# MainBoard.net
KiCad netlist of a schematic drawn in Altium Designer
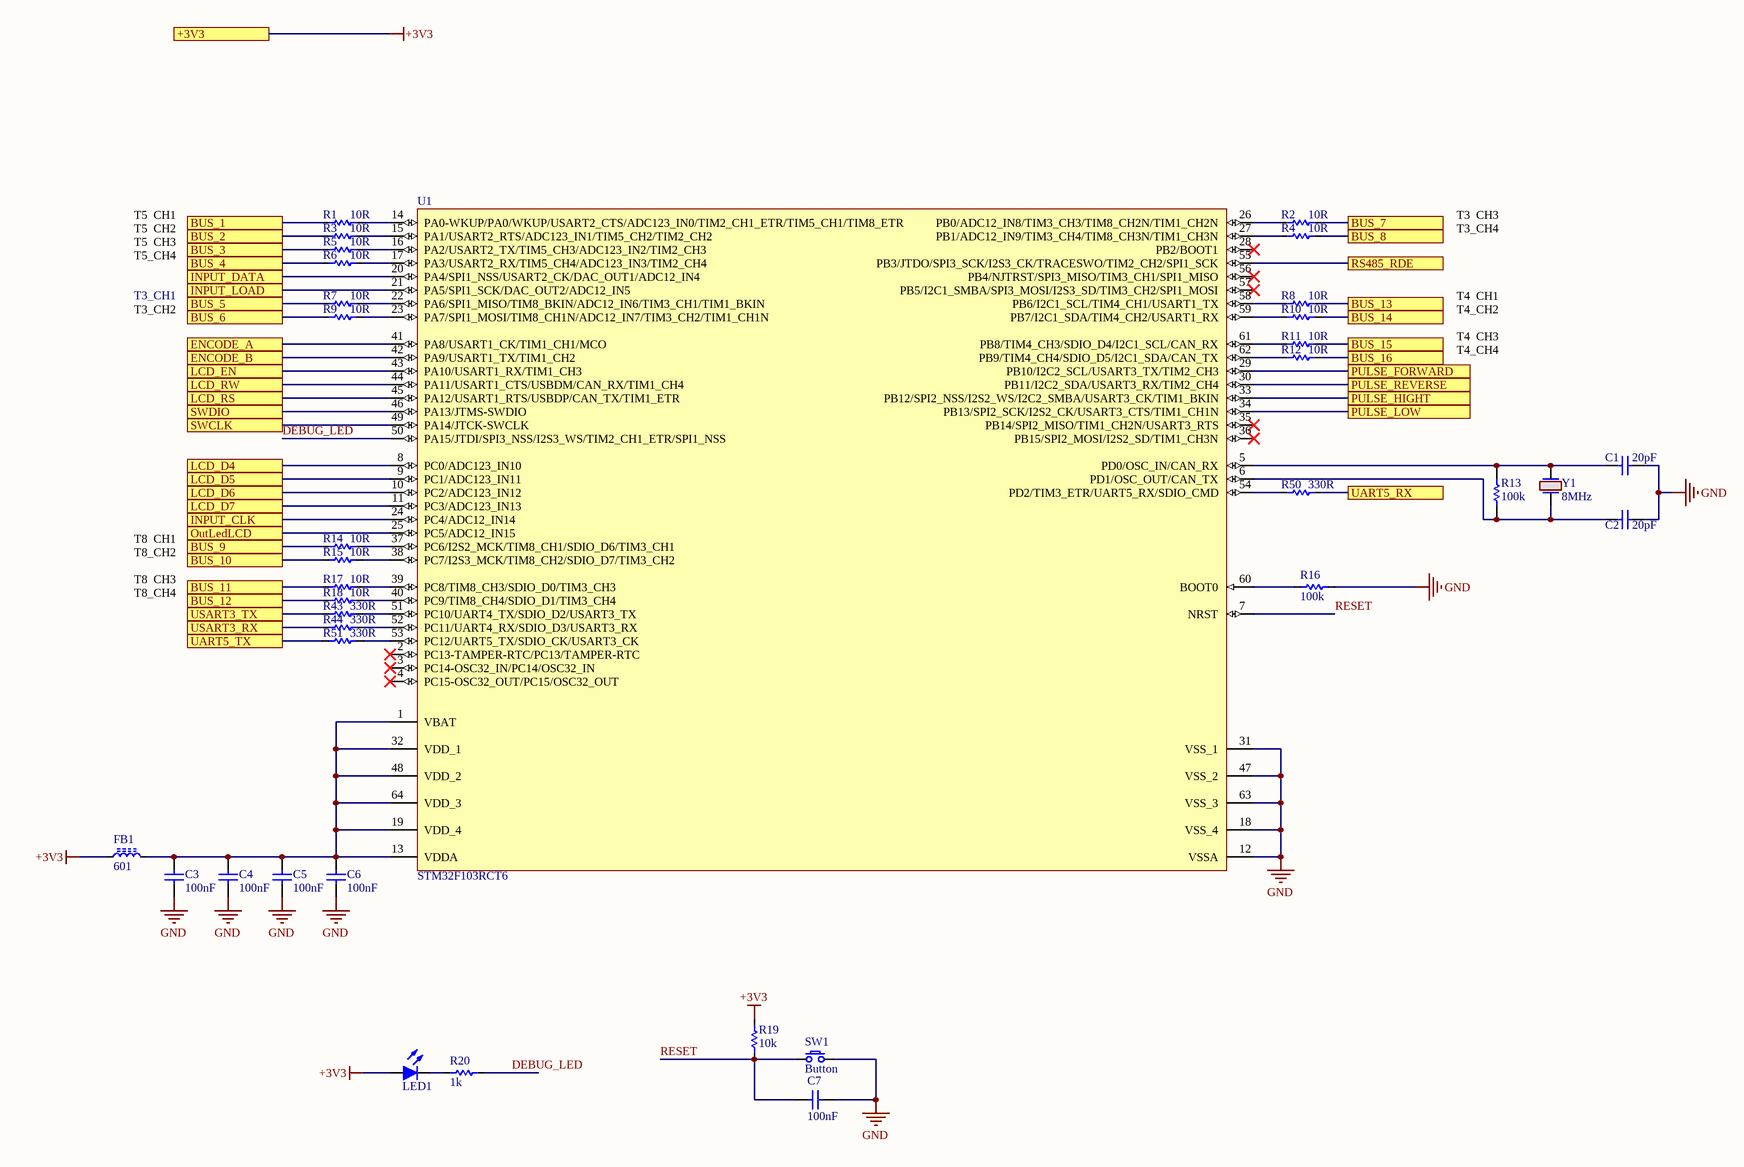
[diagram p0: MainBoard.SchDoc]

(export (version "E")
  (design (tool "Eeschema 10.0.6"))
  (components
    (comp (ref "C1")
      (value "20pF")
      (footprint "C 0603 (1608)")
      (description "Capacitor non-pol")
      (libsource (lib "BKIT4U_LIB") (part "Capacitor NP"))
    )
    (comp (ref "C2")
      (value "20pF")
      (footprint "C 0603 (1608)")
      (description "Capacitor non-pol")
      (libsource (lib "BKIT4U_LIB") (part "Capacitor NP"))
    )
    (comp (ref "C3")
      (value "100nF")
      (footprint "C 0805 (2012)")
      (description "Capacitor non-pol")
      (libsource (lib "BKIT4U_LIB_NEW") (part "Capacitor NP"))
    )
    (comp (ref "C4")
      (value "100nF")
      (footprint "C 0805 (2012)")
      (description "Capacitor non-pol")
      (libsource (lib "BKIT4U_LIB_NEW") (part "Capacitor NP"))
    )
    (comp (ref "C5")
      (value "100nF")
      (footprint "C 0805 (2012)")
      (description "Capacitor non-pol")
      (libsource (lib "BKIT4U_LIB_NEW") (part "Capacitor NP"))
    )
    (comp (ref "C6")
      (value "100nF")
      (footprint "C 0805 (2012)")
      (description "Capacitor non-pol")
      (libsource (lib "BKIT4U_LIB_NEW") (part "Capacitor NP"))
    )
    (comp (ref "C7")
      (value "100nF")
      (footprint "C 0805 (2012)")
      (description "Capacitor non-pol")
      (libsource (lib "BKIT4U_LIB_NEW") (part "Capacitor NP"))
    )
    (comp (ref "FB1")
      (value "601")
      (footprint "Inductor SMD 0805 (2012)")
      (description "Ferrite Breab")
      (libsource (lib "BKIT4U_LIB_NEW") (part "Ferrite Breab"))
    )
    (comp (ref "LED1")
      (value "Led")
      (footprint "Led SMD 0603")
      (description "Typical LED")
      (libsource (lib "BKIT4U_LIB_NEW") (part "Led"))
    )
    (comp (ref "R1")
      (value "10R")
      (footprint "R 0603 (1608)")
      (description "Resistor")
      (fields (field (name "PUBLISHER") "Altium Limited"))
      (libsource (lib "BKIT4U_LIB_NEW") (part "Resistor"))
    )
    (comp (ref "R2")
      (value "10R")
      (footprint "R 0603 (1608)")
      (description "Resistor")
      (fields (field (name "PUBLISHER") "Altium Limited"))
      (libsource (lib "BKIT4U_LIB_NEW") (part "Resistor"))
    )
    (comp (ref "R3")
      (value "10R")
      (footprint "R 0603 (1608)")
      (description "Resistor")
      (fields (field (name "PUBLISHER") "Altium Limited"))
      (libsource (lib "BKIT4U_LIB_NEW") (part "Resistor"))
    )
    (comp (ref "R4")
      (value "10R")
      (footprint "R 0603 (1608)")
      (description "Resistor")
      (fields (field (name "PUBLISHER") "Altium Limited"))
      (libsource (lib "BKIT4U_LIB_NEW") (part "Resistor"))
    )
    (comp (ref "R5")
      (value "10R")
      (footprint "R 0603 (1608)")
      (description "Resistor")
      (fields (field (name "PUBLISHER") "Altium Limited"))
      (libsource (lib "BKIT4U_LIB_NEW") (part "Resistor"))
    )
    (comp (ref "R6")
      (value "10R")
      (footprint "R 0603 (1608)")
      (description "Resistor")
      (fields (field (name "PUBLISHER") "Altium Limited"))
      (libsource (lib "BKIT4U_LIB_NEW") (part "Resistor"))
    )
    (comp (ref "R7")
      (value "10R")
      (footprint "R 0603 (1608)")
      (description "Resistor")
      (fields (field (name "PUBLISHER") "Altium Limited"))
      (libsource (lib "BKIT4U_LIB_NEW") (part "Resistor"))
    )
    (comp (ref "R8")
      (value "10R")
      (footprint "R 0603 (1608)")
      (description "Resistor")
      (fields (field (name "PUBLISHER") "Altium Limited"))
      (libsource (lib "BKIT4U_LIB_NEW") (part "Resistor"))
    )
    (comp (ref "R9")
      (value "10R")
      (footprint "R 0603 (1608)")
      (description "Resistor")
      (fields (field (name "PUBLISHER") "Altium Limited"))
      (libsource (lib "BKIT4U_LIB_NEW") (part "Resistor"))
    )
    (comp (ref "R10")
      (value "10R")
      (footprint "R 0603 (1608)")
      (description "Resistor")
      (fields (field (name "PUBLISHER") "Altium Limited"))
      (libsource (lib "BKIT4U_LIB_NEW") (part "Resistor"))
    )
    (comp (ref "R11")
      (value "10R")
      (footprint "R 0603 (1608)")
      (description "Resistor")
      (fields (field (name "PUBLISHER") "Altium Limited"))
      (libsource (lib "BKIT4U_LIB_NEW") (part "Resistor"))
    )
    (comp (ref "R12")
      (value "10R")
      (footprint "R 0603 (1608)")
      (description "Resistor")
      (fields (field (name "PUBLISHER") "Altium Limited"))
      (libsource (lib "BKIT4U_LIB_NEW") (part "Resistor"))
    )
    (comp (ref "R13")
      (value "100k")
      (footprint "R 0603 (1608)")
      (description "Resistor")
      (fields (field (name "PUBLISHER") "Altium Limited"))
      (libsource (lib "BKIT4U_LIB") (part "Resistor"))
    )
    (comp (ref "R14")
      (value "10R")
      (footprint "R 0603 (1608)")
      (description "Resistor")
      (fields (field (name "PUBLISHER") "Altium Limited"))
      (libsource (lib "BKIT4U_LIB_NEW") (part "Resistor"))
    )
    (comp (ref "R15")
      (value "10R")
      (footprint "R 0603 (1608)")
      (description "Resistor")
      (fields (field (name "PUBLISHER") "Altium Limited"))
      (libsource (lib "BKIT4U_LIB_NEW") (part "Resistor"))
    )
    (comp (ref "R16")
      (value "100k")
      (footprint "R 0603 (1608)")
      (description "Resistor")
      (fields (field (name "PUBLISHER") "Altium Limited"))
      (libsource (lib "BKIT4U_LIB_NEW") (part "Resistor"))
    )
    (comp (ref "R17")
      (value "10R")
      (footprint "R 0603 (1608)")
      (description "Resistor")
      (fields (field (name "PUBLISHER") "Altium Limited"))
      (libsource (lib "BKIT4U_LIB_NEW") (part "Resistor"))
    )
    (comp (ref "R18")
      (value "10R")
      (footprint "R 0603 (1608)")
      (description "Resistor")
      (fields (field (name "PUBLISHER") "Altium Limited"))
      (libsource (lib "BKIT4U_LIB_NEW") (part "Resistor"))
    )
    (comp (ref "R19")
      (value "10k")
      (footprint "R 0805 (2012)")
      (description "Resistor")
      (fields (field (name "PUBLISHER") "Altium Limited"))
      (libsource (lib "BKIT4U_LIB_NEW") (part "Resistor"))
    )
    (comp (ref "R20")
      (value "1k")
      (footprint "R 0603 (1608)")
      (description "Resistor")
      (fields (field (name "PUBLISHER") "Altium Limited"))
      (libsource (lib "BKIT4U_LIB_NEW") (part "Resistor"))
    )
    (comp (ref "R43")
      (value "330R")
      (footprint "R 0603 (1608)")
      (description "Resistor")
      (fields (field (name "PUBLISHER") "Altium Limited"))
      (libsource (lib "BKIT4U_LIB_NEW") (part "Resistor"))
    )
    (comp (ref "R44")
      (value "330R")
      (footprint "R 0603 (1608)")
      (description "Resistor")
      (fields (field (name "PUBLISHER") "Altium Limited"))
      (libsource (lib "BKIT4U_LIB_NEW") (part "Resistor"))
    )
    (comp (ref "R50")
      (value "330R")
      (footprint "R 0603 (1608)")
      (description "Resistor")
      (fields (field (name "PUBLISHER") "Altium Limited"))
      (libsource (lib "BKIT4U_LIB_NEW") (part "Resistor"))
    )
    (comp (ref "R51")
      (value "330R")
      (footprint "R 0603 (1608)")
      (description "Resistor")
      (fields (field (name "PUBLISHER") "Altium Limited"))
      (libsource (lib "BKIT4U_LIB_NEW") (part "Resistor"))
    )
    (comp (ref "SW1")
      (value "Button")
      (footprint "SW/2/SMD")
      (description "Tact switch 2 pin")
      (libsource (lib "BKIT4U_LIB_NEW") (part "SW SPST"))
    )
    (comp (ref "U1")
      (value "STM32F103RCT6")
      (footprint "LQFP64_N")
      (libsource (lib "BKIT4U_LIB_NEW") (part "STM32F103RCT6"))
    )
    (comp (ref "Y1")
      (value "8MHz")
      (footprint "Crystal SMD FC135")
      (libsource (lib "BKIT4U_LIB") (part "Crystal"))
    )
  )
  (nets
    (net (code "1") (name "+3V3") (class "Default")
      (node (ref "FB1") (pin "1") (pinfunction "1_1") (pintype "passive"))
      (node (ref "LED1") (pin "2") (pinfunction "A_2") (pintype "passive"))
      (node (ref "R19") (pin "2") (pinfunction "2_2") (pintype "passive"))
    )
    (net (code "2") (name "/BUS_1") (class "Default")
      (node (ref "R1") (pin "1") (pinfunction "1_1") (pintype "passive"))
    )
    (net (code "3") (name "/BUS_2") (class "Default")
      (node (ref "R3") (pin "1") (pinfunction "1_1") (pintype "passive"))
    )
    (net (code "4") (name "/BUS_3") (class "Default")
      (node (ref "R5") (pin "1") (pinfunction "1_1") (pintype "passive"))
    )
    (net (code "5") (name "/BUS_4") (class "Default")
      (node (ref "R6") (pin "1") (pinfunction "1_1") (pintype "passive"))
    )
    (net (code "6") (name "/BUS_5") (class "Default")
      (node (ref "R7") (pin "1") (pinfunction "1_1") (pintype "passive"))
    )
    (net (code "7") (name "/BUS_6") (class "Default")
      (node (ref "R9") (pin "1") (pinfunction "1_1") (pintype "passive"))
    )
    (net (code "8") (name "/BUS_7") (class "Default")
      (node (ref "R2") (pin "2") (pinfunction "2_2") (pintype "passive"))
    )
    (net (code "9") (name "/BUS_8") (class "Default")
      (node (ref "R4") (pin "2") (pinfunction "2_2") (pintype "passive"))
    )
    (net (code "10") (name "/BUS_9") (class "Default")
      (node (ref "R14") (pin "1") (pinfunction "1_1") (pintype "passive"))
    )
    (net (code "11") (name "/BUS_10") (class "Default")
      (node (ref "R15") (pin "1") (pinfunction "1_1") (pintype "passive"))
    )
    (net (code "12") (name "/BUS_11") (class "Default")
      (node (ref "R17") (pin "1") (pinfunction "1_1") (pintype "passive"))
    )
    (net (code "13") (name "/BUS_12") (class "Default")
      (node (ref "R18") (pin "1") (pinfunction "1_1") (pintype "passive"))
    )
    (net (code "14") (name "/BUS_13") (class "Default")
      (node (ref "R8") (pin "2") (pinfunction "2_2") (pintype "passive"))
    )
    (net (code "15") (name "/BUS_14") (class "Default")
      (node (ref "R10") (pin "2") (pinfunction "2_2") (pintype "passive"))
    )
    (net (code "16") (name "/BUS_15") (class "Default")
      (node (ref "R11") (pin "2") (pinfunction "2_2") (pintype "passive"))
    )
    (net (code "17") (name "/BUS_16") (class "Default")
      (node (ref "R12") (pin "2") (pinfunction "2_2") (pintype "passive"))
    )
    (net (code "18") (name "/DEBUG_LED") (class "Default")
      (node (ref "R20") (pin "2") (pinfunction "2_2") (pintype "passive"))
      (node (ref "U1") (pin "50") (pinfunction "PA15/JTDI/SPI3_NSS/I2S3_WS/TIM2_CH1_ETR/SPI1_NSS_50") (pintype "bidirectional"))
    )
    (net (code "19") (name "/ENCODE_A") (class "Default")
      (node (ref "U1") (pin "41") (pinfunction "PA8/USART1_CK/TIM1_CH1/MCO_41") (pintype "bidirectional"))
    )
    (net (code "20") (name "/ENCODE_B") (class "Default")
      (node (ref "U1") (pin "42") (pinfunction "PA9/USART1_TX/TIM1_CH2_42") (pintype "bidirectional"))
    )
    (net (code "21") (name "/INPUT_CLK") (class "Default")
      (node (ref "U1") (pin "24") (pinfunction "PC4/ADC12_IN14_24") (pintype "bidirectional"))
    )
    (net (code "22") (name "/INPUT_DATA") (class "Default")
      (node (ref "U1") (pin "20") (pinfunction "PA4/SPI1_NSS/USART2_CK/DAC_OUT1/ADC12_IN4_20") (pintype "bidirectional"))
    )
    (net (code "23") (name "/INPUT_LOAD") (class "Default")
      (node (ref "U1") (pin "21") (pinfunction "PA5/SPI1_SCK/DAC_OUT2/ADC12_IN5_21") (pintype "bidirectional"))
    )
    (net (code "24") (name "/LCD_D4") (class "Default")
      (node (ref "U1") (pin "8") (pinfunction "PC0/ADC123_IN10_8") (pintype "bidirectional"))
    )
    (net (code "25") (name "/LCD_D5") (class "Default")
      (node (ref "U1") (pin "9") (pinfunction "PC1/ADC123_IN11_9") (pintype "bidirectional"))
    )
    (net (code "26") (name "/LCD_D6") (class "Default")
      (node (ref "U1") (pin "10") (pinfunction "PC2/ADC123_IN12_10") (pintype "bidirectional"))
    )
    (net (code "27") (name "/LCD_D7") (class "Default")
      (node (ref "U1") (pin "11") (pinfunction "PC3/ADC123_IN13_11") (pintype "bidirectional"))
    )
    (net (code "28") (name "/LCD_EN") (class "Default")
      (node (ref "U1") (pin "43") (pinfunction "PA10/USART1_RX/TIM1_CH3_43") (pintype "bidirectional"))
    )
    (net (code "29") (name "/LCD_RS") (class "Default")
      (node (ref "U1") (pin "45") (pinfunction "PA12/USART1_RTS/USBDP/CAN_TX/TIM1_ETR_45") (pintype "bidirectional"))
    )
    (net (code "30") (name "/LCD_RW") (class "Default")
      (node (ref "U1") (pin "44") (pinfunction "PA11/USART1_CTS/USBDM/CAN_RX/TIM1_CH4_44") (pintype "bidirectional"))
    )
    (net (code "31") (name "/OutLedLCD") (class "Default")
      (node (ref "U1") (pin "25") (pinfunction "PC5/ADC12_IN15_25") (pintype "bidirectional"))
    )
    (net (code "32") (name "/PULSE_FORWARD") (class "Default")
      (node (ref "U1") (pin "29") (pinfunction "PB10/I2C2_SCL/USART3_TX/TIM2_CH3_29") (pintype "bidirectional"))
    )
    (net (code "33") (name "/PULSE_HIGHT") (class "Default")
      (node (ref "U1") (pin "33") (pinfunction "PB12/SPI2_NSS/I2S2_WS/I2C2_SMBA/USART3_CK/TIM1_BKIN_33") (pintype "bidirectional"))
    )
    (net (code "34") (name "/PULSE_LOW") (class "Default")
      (node (ref "U1") (pin "34") (pinfunction "PB13/SPI2_SCK/I2S2_CK/USART3_CTS/TIM1_CH1N_34") (pintype "bidirectional"))
    )
    (net (code "35") (name "/PULSE_REVERSE") (class "Default")
      (node (ref "U1") (pin "30") (pinfunction "PB11/I2C2_SDA/USART3_RX/TIM2_CH4_30") (pintype "bidirectional"))
    )
    (net (code "36") (name "/RESET") (class "Default")
      (node (ref "C7") (pin "1") (pinfunction "1_1") (pintype "passive"))
      (node (ref "R19") (pin "1") (pinfunction "1_1") (pintype "passive"))
      (node (ref "SW1") (pin "1") (pinfunction "1_1") (pintype "passive"))
      (node (ref "U1") (pin "7") (pinfunction "NRST_7") (pintype "bidirectional"))
    )
    (net (code "37") (name "/RS485_RDE") (class "Default")
      (node (ref "U1") (pin "55") (pinfunction "PB3/JTDO/SPI3_SCK/I2S3_CK/TRACESWO/TIM2_CH2/SPI1_SCK_55") (pintype "bidirectional"))
    )
    (net (code "38") (name "/SWCLK") (class "Default")
      (node (ref "U1") (pin "49") (pinfunction "PA14/JTCK-SWCLK_49") (pintype "bidirectional"))
    )
    (net (code "39") (name "/SWDIO") (class "Default")
      (node (ref "U1") (pin "46") (pinfunction "PA13/JTMS-SWDIO_46") (pintype "bidirectional"))
    )
    (net (code "40") (name "/UART5_RX") (class "Default")
      (node (ref "R50") (pin "2") (pinfunction "2_2") (pintype "passive"))
    )
    (net (code "41") (name "/UART5_TX") (class "Default")
      (node (ref "R51") (pin "1") (pinfunction "1_1") (pintype "passive"))
    )
    (net (code "42") (name "/USART3_RX") (class "Default")
      (node (ref "R44") (pin "1") (pinfunction "1_1") (pintype "passive"))
    )
    (net (code "43") (name "/USART3_TX") (class "Default")
      (node (ref "R43") (pin "1") (pinfunction "1_1") (pintype "passive"))
    )
    (net (code "44") (name "GND") (class "Default")
      (node (ref "C1") (pin "2") (pinfunction "2_2") (pintype "passive"))
      (node (ref "C2") (pin "2") (pinfunction "2_2") (pintype "passive"))
      (node (ref "C3") (pin "2") (pinfunction "2_2") (pintype "passive"))
      (node (ref "C4") (pin "2") (pinfunction "2_2") (pintype "passive"))
      (node (ref "C5") (pin "2") (pinfunction "2_2") (pintype "passive"))
      (node (ref "C6") (pin "2") (pinfunction "2_2") (pintype "passive"))
      (node (ref "C7") (pin "2") (pinfunction "2_2") (pintype "passive"))
      (node (ref "R16") (pin "2") (pinfunction "2_2") (pintype "passive"))
      (node (ref "SW1") (pin "2") (pinfunction "2_2") (pintype "passive"))
      (node (ref "U1") (pin "12") (pinfunction "VSSA_12") (pintype "power_in"))
      (node (ref "U1") (pin "18") (pinfunction "VSS_4_18") (pintype "power_in"))
      (node (ref "U1") (pin "31") (pinfunction "VSS_1_31") (pintype "power_in"))
      (node (ref "U1") (pin "47") (pinfunction "VSS_2_47") (pintype "power_in"))
      (node (ref "U1") (pin "63") (pinfunction "VSS_3_63") (pintype "power_in"))
    )
    (net (code "45") (name "Net-(LED1-K)") (class "Default")
      (node (ref "LED1") (pin "1") (pinfunction "K_1") (pintype "passive"))
      (node (ref "R20") (pin "1") (pinfunction "1_1") (pintype "passive"))
    )
    (net (code "46") (name "Net-(U1-BOOT0)") (class "Default")
      (node (ref "R16") (pin "1") (pinfunction "1_1") (pintype "passive"))
      (node (ref "U1") (pin "60") (pinfunction "BOOT0_60") (pintype "input"))
    )
    (net (code "47") (name "Net-(U1-PA0-WKUP{slash}PA0{slash}WKUP{slash}USART2_CTS{slash}ADC123_IN0{slash}TIM2_CH1_ETR{slash}TIM5_CH1{slash}TIM8_ETR)") (class "Default")
      (node (ref "R1") (pin "2") (pinfunction "2_2") (pintype "passive"))
      (node (ref "U1") (pin "14") (pinfunction "PA0-WKUP/PA0/WKUP/USART2_CTS/ADC123_IN0/TIM2_CH1_ETR/TIM5_CH1/TIM8_ETR_14") (pintype "bidirectional"))
    )
    (net (code "48") (name "Net-(U1-PA1{slash}USART2_RTS{slash}ADC123_IN1{slash}TIM5_CH2{slash}TIM2_CH2)") (class "Default")
      (node (ref "R3") (pin "2") (pinfunction "2_2") (pintype "passive"))
      (node (ref "U1") (pin "15") (pinfunction "PA1/USART2_RTS/ADC123_IN1/TIM5_CH2/TIM2_CH2_15") (pintype "bidirectional"))
    )
    (net (code "49") (name "Net-(U1-PA2{slash}USART2_TX{slash}TIM5_CH3{slash}ADC123_IN2{slash}TIM2_CH3)") (class "Default")
      (node (ref "R5") (pin "2") (pinfunction "2_2") (pintype "passive"))
      (node (ref "U1") (pin "16") (pinfunction "PA2/USART2_TX/TIM5_CH3/ADC123_IN2/TIM2_CH3_16") (pintype "bidirectional"))
    )
    (net (code "50") (name "Net-(U1-PA3{slash}USART2_RX{slash}TIM5_CH4{slash}ADC123_IN3{slash}TIM2_CH4)") (class "Default")
      (node (ref "R6") (pin "2") (pinfunction "2_2") (pintype "passive"))
      (node (ref "U1") (pin "17") (pinfunction "PA3/USART2_RX/TIM5_CH4/ADC123_IN3/TIM2_CH4_17") (pintype "bidirectional"))
    )
    (net (code "51") (name "Net-(U1-PA6{slash}SPI1_MISO{slash}TIM8_BKIN{slash}ADC12_IN6{slash}TIM3_CH1{slash}TIM1_BKIN)") (class "Default")
      (node (ref "R7") (pin "2") (pinfunction "2_2") (pintype "passive"))
      (node (ref "U1") (pin "22") (pinfunction "PA6/SPI1_MISO/TIM8_BKIN/ADC12_IN6/TIM3_CH1/TIM1_BKIN_22") (pintype "bidirectional"))
    )
    (net (code "52") (name "Net-(U1-PA7{slash}SPI1_MOSI{slash}TIM8_CH1N{slash}ADC12_IN7{slash}TIM3_CH2{slash}TIM1_CH1N)") (class "Default")
      (node (ref "R9") (pin "2") (pinfunction "2_2") (pintype "passive"))
      (node (ref "U1") (pin "23") (pinfunction "PA7/SPI1_MOSI/TIM8_CH1N/ADC12_IN7/TIM3_CH2/TIM1_CH1N_23") (pintype "bidirectional"))
    )
    (net (code "53") (name "Net-(U1-PB0{slash}ADC12_IN8{slash}TIM3_CH3{slash}TIM8_CH2N{slash}TIM1_CH2N)") (class "Default")
      (node (ref "R2") (pin "1") (pinfunction "1_1") (pintype "passive"))
      (node (ref "U1") (pin "26") (pinfunction "PB0/ADC12_IN8/TIM3_CH3/TIM8_CH2N/TIM1_CH2N_26") (pintype "bidirectional"))
    )
    (net (code "54") (name "Net-(U1-PB1{slash}ADC12_IN9{slash}TIM3_CH4{slash}TIM8_CH3N{slash}TIM1_CH3N)") (class "Default")
      (node (ref "R4") (pin "1") (pinfunction "1_1") (pintype "passive"))
      (node (ref "U1") (pin "27") (pinfunction "PB1/ADC12_IN9/TIM3_CH4/TIM8_CH3N/TIM1_CH3N_27") (pintype "bidirectional"))
    )
    (net (code "55") (name "Net-(U1-PB6{slash}I2C1_SCL{slash}TIM4_CH1{slash}USART1_TX)") (class "Default")
      (node (ref "R8") (pin "1") (pinfunction "1_1") (pintype "passive"))
      (node (ref "U1") (pin "58") (pinfunction "PB6/I2C1_SCL/TIM4_CH1/USART1_TX_58") (pintype "bidirectional"))
    )
    (net (code "56") (name "Net-(U1-PB7{slash}I2C1_SDA{slash}TIM4_CH2{slash}USART1_RX)") (class "Default")
      (node (ref "R10") (pin "1") (pinfunction "1_1") (pintype "passive"))
      (node (ref "U1") (pin "59") (pinfunction "PB7/I2C1_SDA/TIM4_CH2/USART1_RX_59") (pintype "bidirectional"))
    )
    (net (code "57") (name "Net-(U1-PB8{slash}TIM4_CH3{slash}SDIO_D4{slash}I2C1_SCL{slash}CAN_RX)") (class "Default")
      (node (ref "R11") (pin "1") (pinfunction "1_1") (pintype "passive"))
      (node (ref "U1") (pin "61") (pinfunction "PB8/TIM4_CH3/SDIO_D4/I2C1_SCL/CAN_RX_61") (pintype "bidirectional"))
    )
    (net (code "58") (name "Net-(U1-PB9{slash}TIM4_CH4{slash}SDIO_D5{slash}I2C1_SDA{slash}CAN_TX)") (class "Default")
      (node (ref "R12") (pin "1") (pinfunction "1_1") (pintype "passive"))
      (node (ref "U1") (pin "62") (pinfunction "PB9/TIM4_CH4/SDIO_D5/I2C1_SDA/CAN_TX_62") (pintype "bidirectional"))
    )
    (net (code "59") (name "Net-(U1-PC6{slash}I2S2_MCK{slash}TIM8_CH1{slash}SDIO_D6{slash}TIM3_CH1)") (class "Default")
      (node (ref "R14") (pin "2") (pinfunction "2_2") (pintype "passive"))
      (node (ref "U1") (pin "37") (pinfunction "PC6/I2S2_MCK/TIM8_CH1/SDIO_D6/TIM3_CH1_37") (pintype "bidirectional"))
    )
    (net (code "60") (name "Net-(U1-PC7{slash}I2S3_MCK{slash}TIM8_CH2{slash}SDIO_D7{slash}TIM3_CH2)") (class "Default")
      (node (ref "R15") (pin "2") (pinfunction "2_2") (pintype "passive"))
      (node (ref "U1") (pin "38") (pinfunction "PC7/I2S3_MCK/TIM8_CH2/SDIO_D7/TIM3_CH2_38") (pintype "bidirectional"))
    )
    (net (code "61") (name "Net-(U1-PC8{slash}TIM8_CH3{slash}SDIO_D0{slash}TIM3_CH3)") (class "Default")
      (node (ref "R17") (pin "2") (pinfunction "2_2") (pintype "passive"))
      (node (ref "U1") (pin "39") (pinfunction "PC8/TIM8_CH3/SDIO_D0/TIM3_CH3_39") (pintype "bidirectional"))
    )
    (net (code "62") (name "Net-(U1-PC9{slash}TIM8_CH4{slash}SDIO_D1{slash}TIM3_CH4)") (class "Default")
      (node (ref "R18") (pin "2") (pinfunction "2_2") (pintype "passive"))
      (node (ref "U1") (pin "40") (pinfunction "PC9/TIM8_CH4/SDIO_D1/TIM3_CH4_40") (pintype "bidirectional"))
    )
    (net (code "63") (name "Net-(U1-PC10{slash}UART4_TX{slash}SDIO_D2{slash}USART3_TX)") (class "Default")
      (node (ref "R43") (pin "2") (pinfunction "2_2") (pintype "passive"))
      (node (ref "U1") (pin "51") (pinfunction "PC10/UART4_TX/SDIO_D2/USART3_TX_51") (pintype "bidirectional"))
    )
    (net (code "64") (name "Net-(U1-PC11{slash}UART4_RX{slash}SDIO_D3{slash}USART3_RX)") (class "Default")
      (node (ref "R44") (pin "2") (pinfunction "2_2") (pintype "passive"))
      (node (ref "U1") (pin "52") (pinfunction "PC11/UART4_RX/SDIO_D3/USART3_RX_52") (pintype "bidirectional"))
    )
    (net (code "65") (name "Net-(U1-PC12{slash}UART5_TX{slash}SDIO_CK{slash}USART3_CK)") (class "Default")
      (node (ref "R51") (pin "2") (pinfunction "2_2") (pintype "passive"))
      (node (ref "U1") (pin "53") (pinfunction "PC12/UART5_TX/SDIO_CK/USART3_CK_53") (pintype "bidirectional"))
    )
    (net (code "66") (name "Net-(U1-PD0{slash}OSC_IN{slash}CAN_RX)") (class "Default")
      (node (ref "C1") (pin "1") (pinfunction "1_1") (pintype "passive"))
      (node (ref "R13") (pin "2") (pinfunction "2_2") (pintype "passive"))
      (node (ref "U1") (pin "5") (pinfunction "PD0/OSC_IN/CAN_RX_5") (pintype "bidirectional"))
      (node (ref "Y1") (pin "2") (pinfunction "2_2") (pintype "passive"))
    )
    (net (code "67") (name "Net-(U1-PD1{slash}OSC_OUT{slash}CAN_TX)") (class "Default")
      (node (ref "C2") (pin "1") (pinfunction "1_1") (pintype "passive"))
      (node (ref "R13") (pin "1") (pinfunction "1_1") (pintype "passive"))
      (node (ref "U1") (pin "6") (pinfunction "PD1/OSC_OUT/CAN_TX_6") (pintype "bidirectional"))
      (node (ref "Y1") (pin "1") (pinfunction "1_1") (pintype "passive"))
    )
    (net (code "68") (name "Net-(U1-PD2{slash}TIM3_ETR{slash}UART5_RX{slash}SDIO_CMD)") (class "Default")
      (node (ref "R50") (pin "1") (pinfunction "1_1") (pintype "passive"))
      (node (ref "U1") (pin "54") (pinfunction "PD2/TIM3_ETR/UART5_RX/SDIO_CMD_54") (pintype "bidirectional"))
    )
    (net (code "69") (name "Net-(U1-VBAT)") (class "Default")
      (node (ref "C3") (pin "1") (pinfunction "1_1") (pintype "passive"))
      (node (ref "C4") (pin "1") (pinfunction "1_1") (pintype "passive"))
      (node (ref "C5") (pin "1") (pinfunction "1_1") (pintype "passive"))
      (node (ref "C6") (pin "1") (pinfunction "1_1") (pintype "passive"))
      (node (ref "FB1") (pin "2") (pinfunction "2_2") (pintype "passive"))
      (node (ref "U1") (pin "1") (pinfunction "VBAT_1") (pintype "power_in"))
      (node (ref "U1") (pin "13") (pinfunction "VDDA_13") (pintype "power_in"))
      (node (ref "U1") (pin "19") (pinfunction "VDD_4_19") (pintype "power_in"))
      (node (ref "U1") (pin "32") (pinfunction "VDD_1_32") (pintype "power_in"))
      (node (ref "U1") (pin "48") (pinfunction "VDD_2_48") (pintype "power_in"))
      (node (ref "U1") (pin "64") (pinfunction "VDD_3_64") (pintype "power_in"))
    )
    (net (code "70") (name "unconnected-(U1-PB2{slash}BOOT1-Pad28)") (class "Default")
      (node (ref "U1") (pin "28") (pinfunction "PB2/BOOT1_28") (pintype "bidirectional+no_connect"))
    )
    (net (code "71") (name "unconnected-(U1-PB4{slash}NJTRST{slash}SPI3_MISO{slash}TIM3_CH1{slash}SPI1_MISO-Pad56)") (class "Default")
      (node (ref "U1") (pin "56") (pinfunction "PB4/NJTRST/SPI3_MISO/TIM3_CH1/SPI1_MISO_56") (pintype "bidirectional+no_connect"))
    )
    (net (code "72") (name "unconnected-(U1-PB5{slash}I2C1_SMBA{slash}SPI3_MOSI{slash}I2S3_SD{slash}TIM3_CH2{slash}SPI1_MOSI-Pad57)") (class "Default")
      (node (ref "U1") (pin "57") (pinfunction "PB5/I2C1_SMBA/SPI3_MOSI/I2S3_SD/TIM3_CH2/SPI1_MOSI_57") (pintype "bidirectional+no_connect"))
    )
    (net (code "73") (name "unconnected-(U1-PB14{slash}SPI2_MISO{slash}TIM1_CH2N{slash}USART3_RTS-Pad35)") (class "Default")
      (node (ref "U1") (pin "35") (pinfunction "PB14/SPI2_MISO/TIM1_CH2N/USART3_RTS_35") (pintype "bidirectional+no_connect"))
    )
    (net (code "74") (name "unconnected-(U1-PB15{slash}SPI2_MOSI{slash}I2S2_SD{slash}TIM1_CH3N-Pad36)") (class "Default")
      (node (ref "U1") (pin "36") (pinfunction "PB15/SPI2_MOSI/I2S2_SD/TIM1_CH3N_36") (pintype "bidirectional+no_connect"))
    )
    (net (code "75") (name "unconnected-(U1-PC13-TAMPER-RTC{slash}PC13{slash}TAMPER-RTC-Pad2)") (class "Default")
      (node (ref "U1") (pin "2") (pinfunction "PC13-TAMPER-RTC/PC13/TAMPER-RTC_2") (pintype "bidirectional+no_connect"))
    )
    (net (code "76") (name "unconnected-(U1-PC14-OSC32_IN{slash}PC14{slash}OSC32_IN-Pad3)") (class "Default")
      (node (ref "U1") (pin "3") (pinfunction "PC14-OSC32_IN/PC14/OSC32_IN_3") (pintype "bidirectional+no_connect"))
    )
    (net (code "77") (name "unconnected-(U1-PC15-OSC32_OUT{slash}PC15{slash}OSC32_OUT-Pad4)") (class "Default")
      (node (ref "U1") (pin "4") (pinfunction "PC15-OSC32_OUT/PC15/OSC32_OUT_4") (pintype "bidirectional+no_connect"))
    )
  )
)
